# BoB_Brain_v05.net
KiCad netlist of a schematic drawn in EAGLE
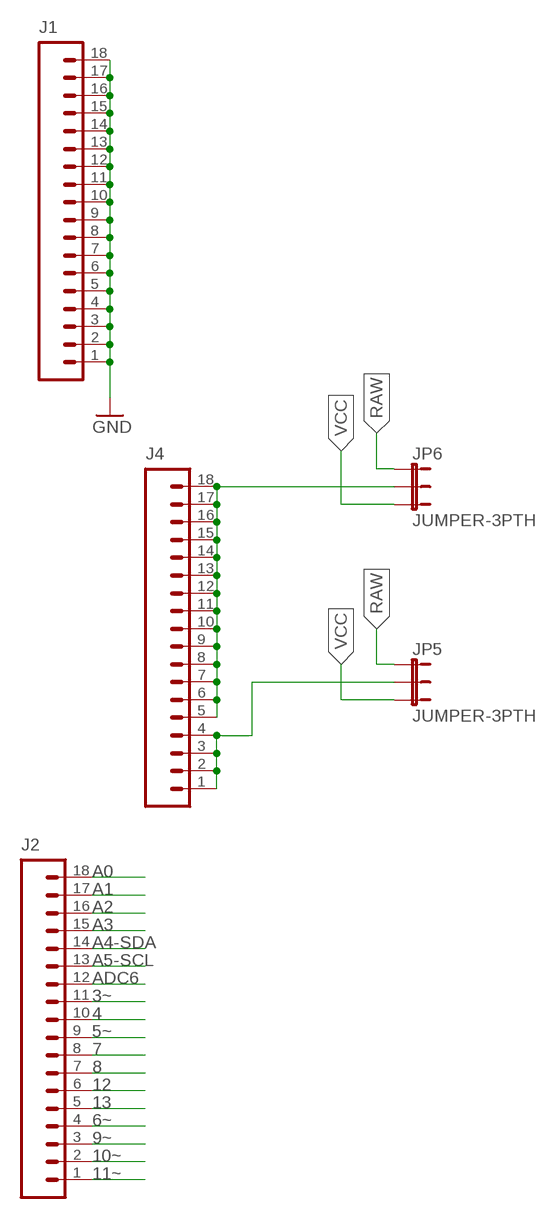
[diagram p0: schematic, sheet 1]
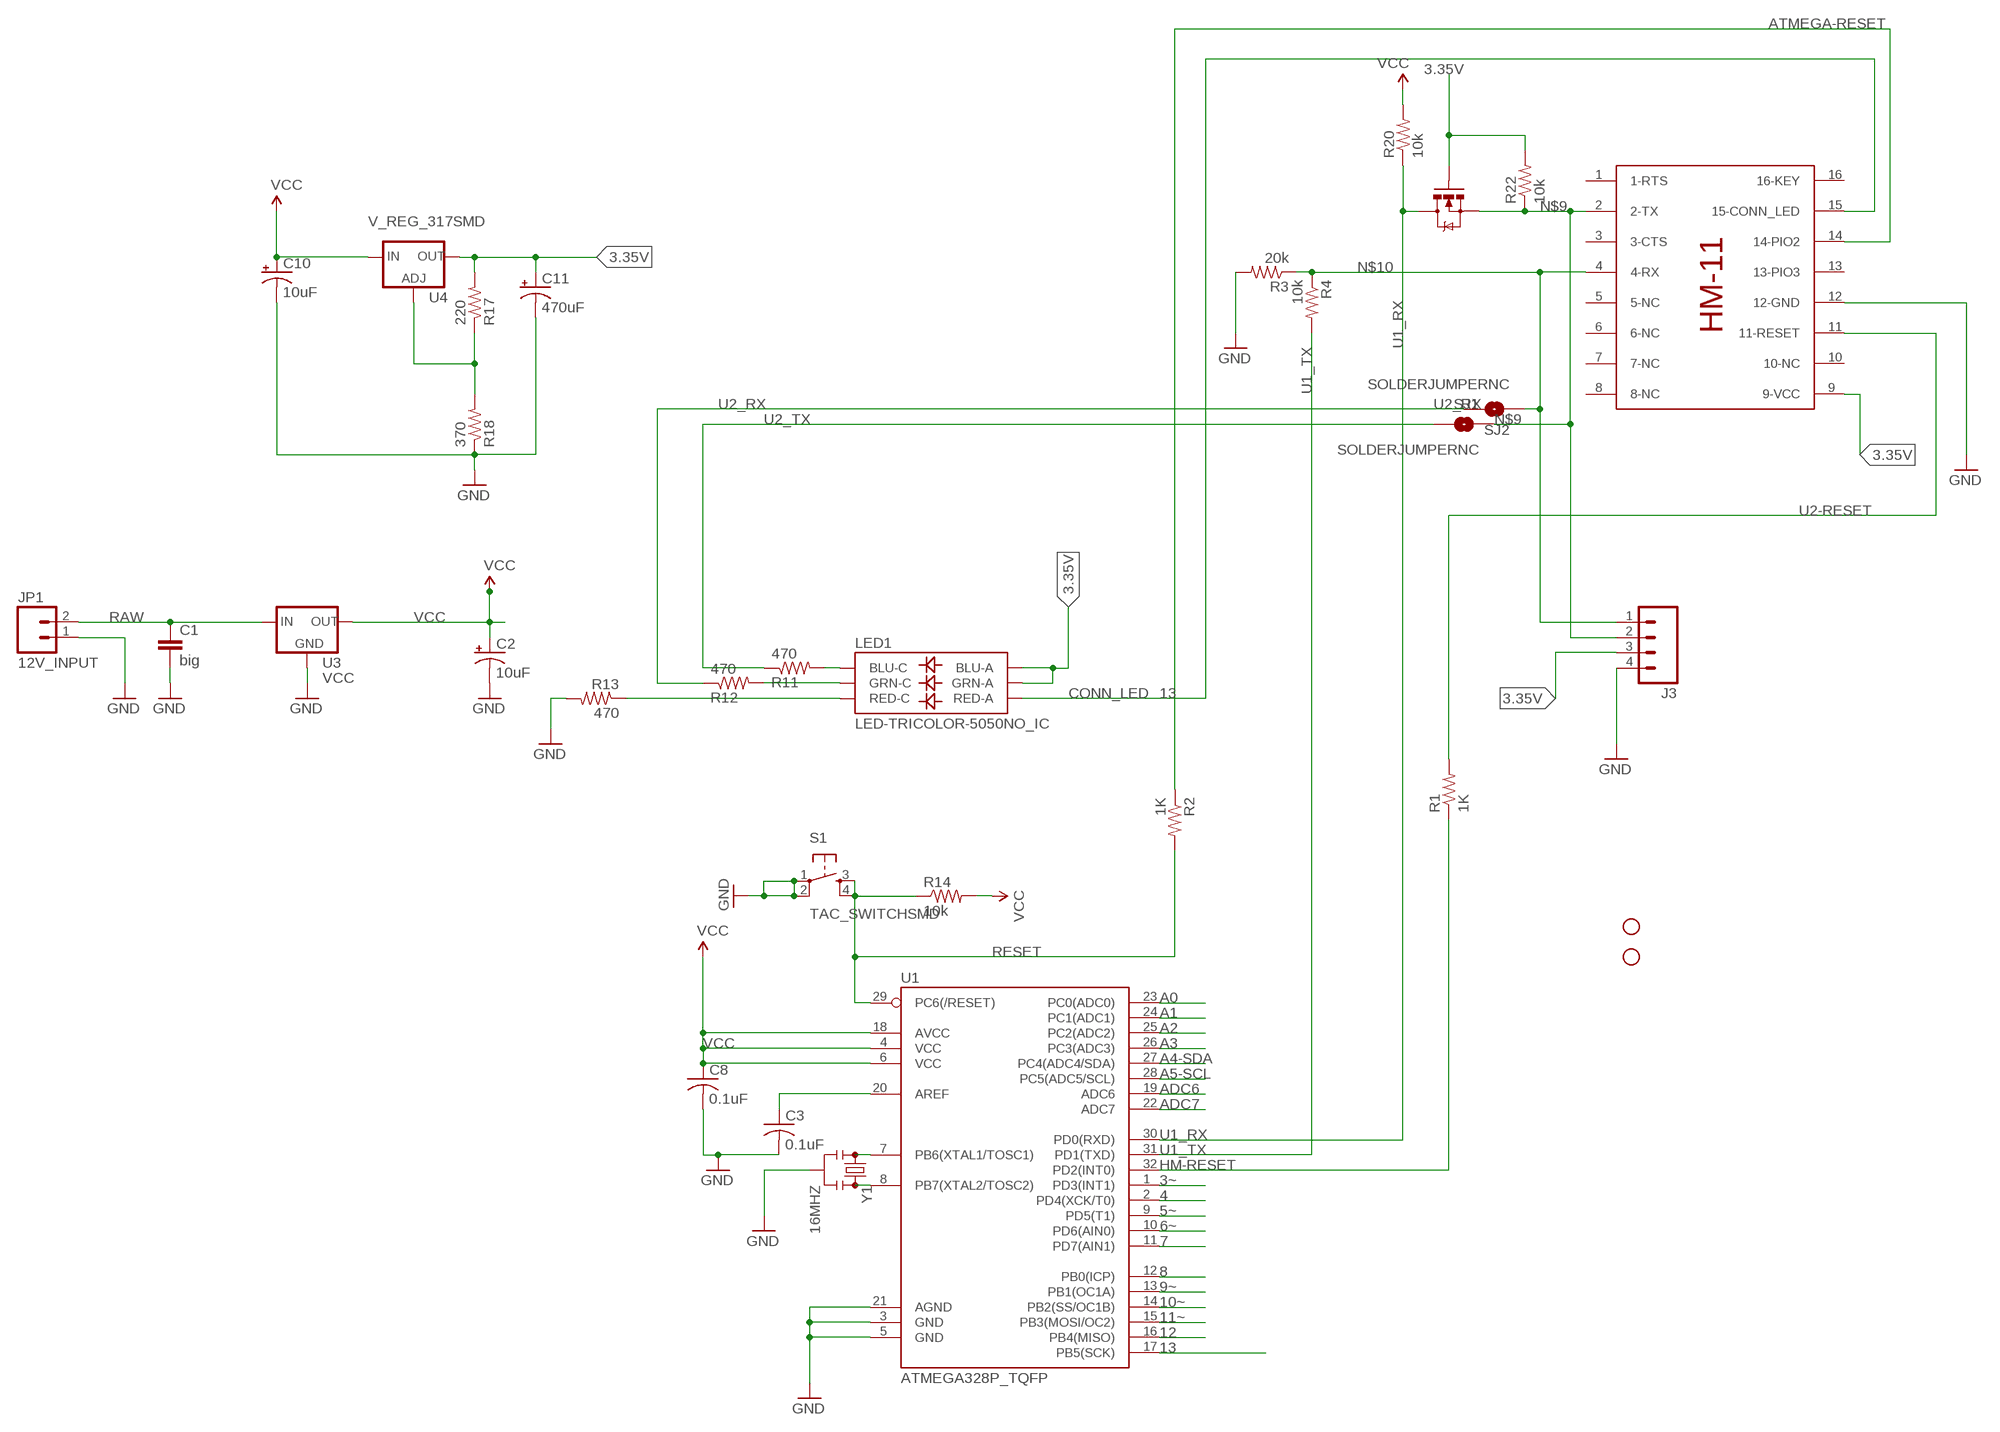
[diagram p1: schematic, sheet 2]

(export (version "E")
  (design (tool "Eeschema 10.0.6"))
  (components
    (comp (ref "C1")
      (value "big")
      (footprint "eagle-import:CAP-PTH-5MM")
      (libsource (lib "eagle-import") (part "CAPPTH1"))
    )
    (comp (ref "C2")
      (value "10uF")
      (footprint "eagle-import:EIA3528")
      (libsource (lib "eagle-import") (part "CAP_POL3528"))
    )
    (comp (ref "C3")
      (value "0.1uF")
      (footprint "eagle-import:C0402")
      (libsource (lib "eagle-import") (part "C-USC0402"))
    )
    (comp (ref "C8")
      (value "0.1uF")
      (footprint "eagle-import:C0402")
      (libsource (lib "eagle-import") (part "C-USC0402"))
    )
    (comp (ref "C10")
      (value "10uF")
      (footprint "eagle-import:EIA3528")
      (libsource (lib "eagle-import") (part "CAP_POL3528"))
    )
    (comp (ref "C11")
      (value "470uF")
      (footprint "eagle-import:CT3528")
      (libsource (lib "eagle-import") (part "CPOL-USCT3528"))
    )
    (comp (ref "H1")
      (value "STAND-OFF")
      (footprint "eagle-import:STAND-OFF")
      (libsource (lib "eagle-import") (part "STAND-OFF"))
    )
    (comp (ref "H2")
      (value "STAND-OFF")
      (footprint "eagle-import:STAND-OFF")
      (libsource (lib "eagle-import") (part "STAND-OFF"))
    )
    (comp (ref "J3")
      (value "M04PTH")
      (footprint "eagle-import:1X04")
      (libsource (lib "eagle-import") (part "M04PTH"))
    )
    (comp (ref "JP1")
      (value "12V_INPUT")
      (footprint "eagle-import:SCREWTERMINAL-5MM-2")
      (libsource (lib "eagle-import") (part "M025MM"))
    )
    (comp (ref "LED1")
      (value "LED-TRICOLOR-5050NO_IC")
      (footprint "eagle-import:LED-TRICOLOR-5050")
      (libsource (lib "eagle-import") (part "LED-TRICOLOR-5050NO_IC"))
    )
    (comp (ref "Q1")
      (value "MOSFET-NCHANNELAO3404A")
      (footprint "eagle-import:SOT23-3")
      (libsource (lib "eagle-import") (part "MOSFET-NCHANNELAO3404A"))
    )
    (comp (ref "R1")
      (value "1K")
      (footprint "eagle-import:R0805W")
      (libsource (lib "eagle-import") (part "R-US_R0805W"))
    )
    (comp (ref "R2")
      (value "1K")
      (footprint "eagle-import:R0805W")
      (libsource (lib "eagle-import") (part "R-US_R0805W"))
    )
    (comp (ref "R3")
      (value "20k")
      (footprint "eagle-import:R0805W")
      (libsource (lib "eagle-import") (part "R-US_R0805W"))
    )
    (comp (ref "R4")
      (value "10k")
      (footprint "eagle-import:R0805W")
      (libsource (lib "eagle-import") (part "R-US_R0805W"))
    )
    (comp (ref "R11")
      (value "470")
      (footprint "eagle-import:R0805W")
      (libsource (lib "eagle-import") (part "R-US_R0805W"))
    )
    (comp (ref "R12")
      (value "470")
      (footprint "eagle-import:R0805W")
      (libsource (lib "eagle-import") (part "R-US_R0805W"))
    )
    (comp (ref "R13")
      (value "470")
      (footprint "eagle-import:R0805W")
      (libsource (lib "eagle-import") (part "R-US_R0805W"))
    )
    (comp (ref "R14")
      (value "10k")
      (footprint "eagle-import:R0805W")
      (libsource (lib "eagle-import") (part "R-US_R0805W"))
    )
    (comp (ref "R17")
      (value "220")
      (footprint "eagle-import:R0805W")
      (libsource (lib "eagle-import") (part "R-US_R0805W"))
    )
    (comp (ref "R18")
      (value "370")
      (footprint "eagle-import:R0805W")
      (libsource (lib "eagle-import") (part "R-US_R0805W"))
    )
    (comp (ref "R20")
      (value "10k")
      (footprint "eagle-import:R0805W")
      (libsource (lib "eagle-import") (part "R-US_R0805W"))
    )
    (comp (ref "R22")
      (value "10k")
      (footprint "eagle-import:R0805W")
      (libsource (lib "eagle-import") (part "R-US_R0805W"))
    )
    (comp (ref "S1")
      (value "TAC_SWITCHSMD")
      (footprint "eagle-import:TACTILE-SWITCH-SMD")
      (libsource (lib "eagle-import") (part "TAC_SWITCHSMD"))
    )
    (comp (ref "SJ1")
      (value "SOLDERJUMPERNC")
      (footprint "eagle-import:SJ_2S")
      (libsource (lib "eagle-import") (part "SOLDERJUMPERNC"))
    )
    (comp (ref "SJ2")
      (value "SOLDERJUMPERNC")
      (footprint "eagle-import:SJ_2S")
      (libsource (lib "eagle-import") (part "SOLDERJUMPERNC"))
    )
    (comp (ref "U$1")
      (value "HM-11")
      (footprint "eagle-import:HM-11")
      (libsource (lib "eagle-import") (part "HM-11"))
    )
    (comp (ref "U1")
      (value "ATMEGA328P_TQFP")
      (footprint "eagle-import:TQFP32-08")
      (libsource (lib "eagle-import") (part "ATMEGA328P_TQFP"))
    )
    (comp (ref "U3")
      (value "VCC")
      (footprint "eagle-import:TO-252")
      (libsource (lib "eagle-import") (part "V_REG_78XX7812"))
    )
    (comp (ref "U4")
      (value "V_REG_317SMD")
      (footprint "eagle-import:SOT223")
      (libsource (lib "eagle-import") (part "V_REG_317SMD"))
    )
    (comp (ref "Y1")
      (value "16MHZ")
      (footprint "eagle-import:RESONATOR-SMD")
      (libsource (lib "eagle-import") (part "RESONATOR16MHZ"))
    )
    (comp (ref "J1")
      (value "M18_")
      (footprint "eagle-import:1X18")
      (libsource (lib "eagle-import") (part "M18_"))
    )
    (comp (ref "J2")
      (value "M18_")
      (footprint "eagle-import:1X18")
      (libsource (lib "eagle-import") (part "M18_"))
    )
    (comp (ref "J4")
      (value "M18_")
      (footprint "eagle-import:1X18")
      (libsource (lib "eagle-import") (part "M18_"))
    )
    (comp (ref "JP5")
      (value "JUMPER-3PTH")
      (footprint "eagle-import:1X03")
      (libsource (lib "eagle-import") (part "JUMPER-3PTH"))
    )
    (comp (ref "JP6")
      (value "JUMPER-3PTH")
      (footprint "eagle-import:1X03")
      (libsource (lib "eagle-import") (part "JUMPER-3PTH"))
    )
  )
  (nets
    (net (code "1") (name "3.35V") (class "Default")
      (node (ref "C11") (pin "-") (pinfunction "+_-") (pintype "passive"))
      (node (ref "J3") (pin "3") (pinfunction "3_3") (pintype "passive"))
      (node (ref "LED1") (pin "1") (pinfunction "GRN-A_1") (pintype "bidirectional"))
      (node (ref "LED1") (pin "3") (pinfunction "BLU-A_3") (pintype "bidirectional"))
      (node (ref "Q1") (pin "1") (pinfunction "G_1") (pintype "passive"))
      (node (ref "R17") (pin "2") (pinfunction "2_2") (pintype "passive"))
      (node (ref "R22") (pin "2") (pinfunction "2_2") (pintype "passive"))
      (node (ref "U$1") (pin "9") (pinfunction "9-VCC_9") (pintype "bidirectional"))
      (node (ref "U4") (pin "2") (pinfunction "OUT_2") (pintype "output"))
    )
    (net (code "2") (name "3~{}") (class "Default")
      (node (ref "J2") (pin "18") (pinfunction "18_18") (pintype "passive"))
      (node (ref "U1") (pin "1") (pinfunction "PD3(INT1)_1") (pintype "bidirectional"))
    )
    (net (code "3") (name "4") (class "Default")
      (node (ref "J2") (pin "17") (pinfunction "17_17") (pintype "passive"))
      (node (ref "U1") (pin "2") (pinfunction "PD4(XCK/T0)_2") (pintype "bidirectional"))
    )
    (net (code "4") (name "5~{}") (class "Default")
      (node (ref "J2") (pin "9") (pinfunction "9_9") (pintype "passive"))
      (node (ref "U1") (pin "9") (pinfunction "PD5(T1)_9") (pintype "bidirectional"))
    )
    (net (code "5") (name "6~{}") (class "Default")
      (node (ref "J2") (pin "4") (pinfunction "4_4") (pintype "passive"))
      (node (ref "U1") (pin "10") (pinfunction "PD6(AIN0)_10") (pintype "bidirectional"))
    )
    (net (code "6") (name "7") (class "Default")
      (node (ref "J2") (pin "8") (pinfunction "8_8") (pintype "passive"))
      (node (ref "U1") (pin "11") (pinfunction "PD7(AIN1)_11") (pintype "bidirectional"))
    )
    (net (code "7") (name "8") (class "Default")
      (node (ref "J2") (pin "7") (pinfunction "7_7") (pintype "passive"))
      (node (ref "U1") (pin "12") (pinfunction "PB0(ICP)_12") (pintype "bidirectional"))
    )
    (net (code "8") (name "9~{}") (class "Default")
      (node (ref "J2") (pin "3") (pinfunction "3_3") (pintype "passive"))
      (node (ref "U1") (pin "13") (pinfunction "PB1(OC1A)_13") (pintype "bidirectional"))
    )
    (net (code "9") (name "10~{}") (class "Default")
      (node (ref "J2") (pin "2") (pinfunction "2_2") (pintype "passive"))
      (node (ref "U1") (pin "14") (pinfunction "PB2(SS/OC1B)_14") (pintype "bidirectional"))
    )
    (net (code "10") (name "11~{}") (class "Default")
      (node (ref "J2") (pin "1") (pinfunction "1_1") (pintype "passive"))
      (node (ref "U1") (pin "15") (pinfunction "PB3(MOSI/OC2)_15") (pintype "bidirectional"))
    )
    (net (code "11") (name "12") (class "Default")
      (node (ref "J2") (pin "6") (pinfunction "6_6") (pintype "passive"))
      (node (ref "U1") (pin "16") (pinfunction "PB4(MISO)_16") (pintype "bidirectional"))
    )
    (net (code "12") (name "13") (class "Default")
      (node (ref "J2") (pin "5") (pinfunction "5_5") (pintype "passive"))
      (node (ref "U1") (pin "17") (pinfunction "PB5(SCK)_17") (pintype "bidirectional"))
    )
    (net (code "13") (name "A0") (class "Default")
      (node (ref "J2") (pin "12") (pinfunction "12_12") (pintype "passive"))
      (node (ref "U1") (pin "23") (pinfunction "PC0(ADC0)_23") (pintype "bidirectional"))
    )
    (net (code "14") (name "A1") (class "Default")
      (node (ref "J2") (pin "10") (pinfunction "10_10") (pintype "passive"))
      (node (ref "U1") (pin "24") (pinfunction "PC1(ADC1)_24") (pintype "bidirectional"))
    )
    (net (code "15") (name "A2") (class "Default")
      (node (ref "J2") (pin "16") (pinfunction "16_16") (pintype "passive"))
      (node (ref "U1") (pin "25") (pinfunction "PC2(ADC2)_25") (pintype "bidirectional"))
    )
    (net (code "16") (name "A3") (class "Default")
      (node (ref "J2") (pin "13") (pinfunction "13_13") (pintype "passive"))
      (node (ref "U1") (pin "26") (pinfunction "PC3(ADC3)_26") (pintype "bidirectional"))
    )
    (net (code "17") (name "A4-SDA") (class "Default")
      (node (ref "J2") (pin "14") (pinfunction "14_14") (pintype "passive"))
      (node (ref "U1") (pin "27") (pinfunction "PC4(ADC4/SDA)_27") (pintype "bidirectional"))
    )
    (net (code "18") (name "A5-SCL") (class "Default")
      (node (ref "J2") (pin "15") (pinfunction "15_15") (pintype "passive"))
      (node (ref "U1") (pin "28") (pinfunction "PC5(ADC5/SCL)_28") (pintype "bidirectional"))
    )
    (net (code "19") (name "ADC6") (class "Default")
      (node (ref "J2") (pin "11") (pinfunction "11_11") (pintype "passive"))
      (node (ref "U1") (pin "19") (pinfunction "ADC6_19") (pintype "bidirectional"))
    )
    (net (code "20") (name "ADC7") (class "Default")
      (node (ref "U1") (pin "22") (pinfunction "ADC7_22") (pintype "bidirectional"))
    )
    (net (code "21") (name "ATMEGA-RESET") (class "Default")
      (node (ref "R2") (pin "1") (pinfunction "1_1") (pintype "passive"))
      (node (ref "U$1") (pin "14") (pinfunction "14-PIO2_14") (pintype "bidirectional"))
    )
    (net (code "22") (name "CONN_LED") (class "Default")
      (node (ref "LED1") (pin "2") (pinfunction "RED-A_2") (pintype "bidirectional"))
      (node (ref "U$1") (pin "15") (pinfunction "15-CONN_LED_15") (pintype "bidirectional"))
    )
    (net (code "23") (name "GND") (class "Default")
      (node (ref "C1") (pin "2") (pinfunction "2_2") (pintype "passive"))
      (node (ref "C10") (pin "C") (pinfunction "-_C") (pintype "passive"))
      (node (ref "C11") (pin "+") (pinfunction "-_+") (pintype "passive"))
      (node (ref "C2") (pin "C") (pinfunction "-_C") (pintype "passive"))
      (node (ref "C3") (pin "2") (pinfunction "2_2") (pintype "passive"))
      (node (ref "C8") (pin "2") (pinfunction "2_2") (pintype "passive"))
      (node (ref "J1") (pin "1") (pinfunction "1_1") (pintype "passive"))
      (node (ref "J1") (pin "10") (pinfunction "10_10") (pintype "passive"))
      (node (ref "J1") (pin "11") (pinfunction "11_11") (pintype "passive"))
      (node (ref "J1") (pin "12") (pinfunction "12_12") (pintype "passive"))
      (node (ref "J1") (pin "13") (pinfunction "13_13") (pintype "passive"))
      (node (ref "J1") (pin "14") (pinfunction "14_14") (pintype "passive"))
      (node (ref "J1") (pin "15") (pinfunction "15_15") (pintype "passive"))
      (node (ref "J1") (pin "16") (pinfunction "16_16") (pintype "passive"))
      (node (ref "J1") (pin "17") (pinfunction "17_17") (pintype "passive"))
      (node (ref "J1") (pin "18") (pinfunction "18_18") (pintype "passive"))
      (node (ref "J1") (pin "2") (pinfunction "2_2") (pintype "passive"))
      (node (ref "J1") (pin "3") (pinfunction "3_3") (pintype "passive"))
      (node (ref "J1") (pin "4") (pinfunction "4_4") (pintype "passive"))
      (node (ref "J1") (pin "5") (pinfunction "5_5") (pintype "passive"))
      (node (ref "J1") (pin "6") (pinfunction "6_6") (pintype "passive"))
      (node (ref "J1") (pin "7") (pinfunction "7_7") (pintype "passive"))
      (node (ref "J1") (pin "8") (pinfunction "8_8") (pintype "passive"))
      (node (ref "J1") (pin "9") (pinfunction "9_9") (pintype "passive"))
      (node (ref "J3") (pin "4") (pinfunction "4_4") (pintype "passive"))
      (node (ref "JP1") (pin "1") (pinfunction "1_1") (pintype "passive"))
      (node (ref "R13") (pin "2") (pinfunction "2_2") (pintype "passive"))
      (node (ref "R18") (pin "1") (pinfunction "1_1") (pintype "passive"))
      (node (ref "R3") (pin "2") (pinfunction "2_2") (pintype "passive"))
      (node (ref "S1") (pin "1") (pinfunction "1_1") (pintype "passive"))
      (node (ref "S1") (pin "2") (pinfunction "2_2") (pintype "passive"))
      (node (ref "U$1") (pin "12") (pinfunction "12-GND_12") (pintype "bidirectional"))
      (node (ref "U1") (pin "21") (pinfunction "AGND_21") (pintype "bidirectional"))
      (node (ref "U1") (pin "3") (pinfunction "GND_3") (pintype "bidirectional"))
      (node (ref "U1") (pin "5") (pinfunction "GND_5") (pintype "bidirectional"))
      (node (ref "U3") (pin "3") (pinfunction "GND_3") (pintype "input"))
      (node (ref "Y1") (pin "2") (pinfunction "2_2") (pintype "passive"))
    )
    (net (code "24") (name "HM-RESET") (class "Default")
      (node (ref "R1") (pin "1") (pinfunction "1_1") (pintype "passive"))
      (node (ref "U1") (pin "32") (pinfunction "PD2(INT0)_32") (pintype "bidirectional"))
    )
    (net (code "25") (name "N$9") (class "Default")
      (node (ref "J3") (pin "2") (pinfunction "2_2") (pintype "passive"))
      (node (ref "Q1") (pin "2") (pinfunction "S_2") (pintype "passive"))
      (node (ref "R22") (pin "1") (pinfunction "1_1") (pintype "passive"))
      (node (ref "SJ1") (pin "1") (pinfunction "1_1") (pintype "passive"))
      (node (ref "U$1") (pin "2") (pinfunction "2-TX_2") (pintype "bidirectional"))
    )
    (net (code "26") (name "N$10") (class "Default")
      (node (ref "J3") (pin "1") (pinfunction "1_1") (pintype "passive"))
      (node (ref "R3") (pin "1") (pinfunction "1_1") (pintype "passive"))
      (node (ref "R4") (pin "1") (pinfunction "1_1") (pintype "passive"))
      (node (ref "SJ2") (pin "1") (pinfunction "1_1") (pintype "passive"))
      (node (ref "U$1") (pin "4") (pinfunction "4-RX_4") (pintype "bidirectional"))
    )
    (net (code "27") (name "Net-(J4-Pad1)") (class "Default")
      (node (ref "J4") (pin "1") (pinfunction "1_1") (pintype "passive"))
      (node (ref "J4") (pin "2") (pinfunction "2_2") (pintype "passive"))
      (node (ref "J4") (pin "3") (pinfunction "3_3") (pintype "passive"))
      (node (ref "J4") (pin "4") (pinfunction "4_4") (pintype "passive"))
      (node (ref "JP5") (pin "2") (pinfunction "2_2") (pintype "passive"))
    )
    (net (code "28") (name "Net-(J4-Pad10)") (class "Default")
      (node (ref "J4") (pin "10") (pinfunction "10_10") (pintype "passive"))
      (node (ref "J4") (pin "11") (pinfunction "11_11") (pintype "passive"))
      (node (ref "J4") (pin "12") (pinfunction "12_12") (pintype "passive"))
      (node (ref "J4") (pin "13") (pinfunction "13_13") (pintype "passive"))
      (node (ref "J4") (pin "14") (pinfunction "14_14") (pintype "passive"))
      (node (ref "J4") (pin "15") (pinfunction "15_15") (pintype "passive"))
      (node (ref "J4") (pin "16") (pinfunction "16_16") (pintype "passive"))
      (node (ref "J4") (pin "17") (pinfunction "17_17") (pintype "passive"))
      (node (ref "J4") (pin "18") (pinfunction "18_18") (pintype "passive"))
      (node (ref "J4") (pin "5") (pinfunction "5_5") (pintype "passive"))
      (node (ref "J4") (pin "6") (pinfunction "6_6") (pintype "passive"))
      (node (ref "J4") (pin "7") (pinfunction "7_7") (pintype "passive"))
      (node (ref "J4") (pin "8") (pinfunction "8_8") (pintype "passive"))
      (node (ref "J4") (pin "9") (pinfunction "9_9") (pintype "passive"))
      (node (ref "JP6") (pin "2") (pinfunction "2_2") (pintype "passive"))
    )
    (net (code "29") (name "Net-(LED1-BLU-C)") (class "Default")
      (node (ref "LED1") (pin "4") (pinfunction "BLU-C_4") (pintype "bidirectional"))
      (node (ref "R11") (pin "2") (pinfunction "2_2") (pintype "passive"))
    )
    (net (code "30") (name "Net-(LED1-GRN-C)") (class "Default")
      (node (ref "LED1") (pin "6") (pinfunction "GRN-C_6") (pintype "bidirectional"))
      (node (ref "R12") (pin "2") (pinfunction "2_2") (pintype "passive"))
    )
    (net (code "31") (name "Net-(LED1-RED-C)") (class "Default")
      (node (ref "LED1") (pin "5") (pinfunction "RED-C_5") (pintype "bidirectional"))
      (node (ref "R13") (pin "1") (pinfunction "1_1") (pintype "passive"))
    )
    (net (code "32") (name "Net-(U1-AREF)") (class "Default")
      (node (ref "C3") (pin "1") (pinfunction "1_1") (pintype "passive"))
      (node (ref "U1") (pin "20") (pinfunction "AREF_20") (pintype "bidirectional"))
    )
    (net (code "33") (name "Net-(U1-PB6(XTAL1{slash}TOSC1))") (class "Default")
      (node (ref "U1") (pin "7") (pinfunction "PB6(XTAL1/TOSC1)_7") (pintype "bidirectional"))
      (node (ref "Y1") (pin "1") (pinfunction "1_1") (pintype "passive"))
    )
    (net (code "34") (name "Net-(U1-PB7(XTAL2{slash}TOSC2))") (class "Default")
      (node (ref "U1") (pin "8") (pinfunction "PB7(XTAL2/TOSC2)_8") (pintype "bidirectional"))
      (node (ref "Y1") (pin "3") (pinfunction "3_3") (pintype "passive"))
    )
    (net (code "35") (name "Net-(U4-ADJ)") (class "Default")
      (node (ref "R17") (pin "1") (pinfunction "1_1") (pintype "passive"))
      (node (ref "R18") (pin "2") (pinfunction "2_2") (pintype "passive"))
      (node (ref "U4") (pin "1") (pinfunction "ADJ_1") (pintype "input"))
    )
    (net (code "36") (name "RAW") (class "Default")
      (node (ref "C1") (pin "1") (pinfunction "1_1") (pintype "passive"))
      (node (ref "JP1") (pin "2") (pinfunction "2_2") (pintype "passive"))
      (node (ref "JP5") (pin "1") (pinfunction "1_1") (pintype "passive"))
      (node (ref "JP6") (pin "1") (pinfunction "1_1") (pintype "passive"))
      (node (ref "U3") (pin "1") (pinfunction "IN_1") (pintype "input"))
    )
    (net (code "37") (name "RESET") (class "Default")
      (node (ref "R14") (pin "1") (pinfunction "1_1") (pintype "passive"))
      (node (ref "R2") (pin "2") (pinfunction "2_2") (pintype "passive"))
      (node (ref "S1") (pin "3") (pinfunction "3_3") (pintype "passive"))
      (node (ref "S1") (pin "4") (pinfunction "4_4") (pintype "passive"))
      (node (ref "U1") (pin "29") (pinfunction "PC6(/RESET)_29") (pintype "bidirectional"))
    )
    (net (code "38") (name "U1_RX") (class "Default")
      (node (ref "Q1") (pin "3") (pinfunction "D_3") (pintype "passive"))
      (node (ref "R20") (pin "1") (pinfunction "1_1") (pintype "passive"))
      (node (ref "U1") (pin "30") (pinfunction "PD0(RXD)_30") (pintype "bidirectional"))
    )
    (net (code "39") (name "U1_TX") (class "Default")
      (node (ref "R4") (pin "2") (pinfunction "2_2") (pintype "passive"))
      (node (ref "U1") (pin "31") (pinfunction "PD1(TXD)_31") (pintype "bidirectional"))
    )
    (net (code "40") (name "U2-RESET") (class "Default")
      (node (ref "R1") (pin "2") (pinfunction "2_2") (pintype "passive"))
      (node (ref "U$1") (pin "11") (pinfunction "11-RESET_11") (pintype "bidirectional"))
    )
    (net (code "41") (name "U2_RX") (class "Default")
      (node (ref "R12") (pin "1") (pinfunction "1_1") (pintype "passive"))
      (node (ref "SJ2") (pin "2") (pinfunction "2_2") (pintype "passive"))
    )
    (net (code "42") (name "U2_TX") (class "Default")
      (node (ref "R11") (pin "1") (pinfunction "1_1") (pintype "passive"))
      (node (ref "SJ1") (pin "2") (pinfunction "2_2") (pintype "passive"))
    )
    (net (code "43") (name "VCC") (class "Default")
      (node (ref "C10") (pin "A") (pinfunction "+_A") (pintype "passive"))
      (node (ref "C2") (pin "A") (pinfunction "+_A") (pintype "passive"))
      (node (ref "C8") (pin "1") (pinfunction "1_1") (pintype "passive"))
      (node (ref "JP5") (pin "3") (pinfunction "3_3") (pintype "passive"))
      (node (ref "JP6") (pin "3") (pinfunction "3_3") (pintype "passive"))
      (node (ref "R14") (pin "2") (pinfunction "2_2") (pintype "passive"))
      (node (ref "R20") (pin "2") (pinfunction "2_2") (pintype "passive"))
      (node (ref "U1") (pin "18") (pinfunction "AVCC_18") (pintype "bidirectional"))
      (node (ref "U1") (pin "4") (pinfunction "VCC_4") (pintype "bidirectional"))
      (node (ref "U1") (pin "6") (pinfunction "VCC_6") (pintype "bidirectional"))
      (node (ref "U3") (pin "2") (pinfunction "OUT_2") (pintype "passive"))
      (node (ref "U4") (pin "3") (pinfunction "IN_3") (pintype "input"))
    )
    (net (code "44") (name "unconnected-(U$1-1-RTS-Pad1)") (class "Default")
      (node (ref "U$1") (pin "1") (pinfunction "1-RTS_1") (pintype "bidirectional"))
    )
    (net (code "45") (name "unconnected-(U$1-3-CTS-Pad3)") (class "Default")
      (node (ref "U$1") (pin "3") (pinfunction "3-CTS_3") (pintype "bidirectional"))
    )
    (net (code "46") (name "unconnected-(U$1-5-NC-Pad5)") (class "Default")
      (node (ref "U$1") (pin "5") (pinfunction "5-NC_5") (pintype "bidirectional"))
    )
    (net (code "47") (name "unconnected-(U$1-6-NC-Pad6)") (class "Default")
      (node (ref "U$1") (pin "6") (pinfunction "6-NC_6") (pintype "bidirectional"))
    )
    (net (code "48") (name "unconnected-(U$1-7-NC-Pad7)") (class "Default")
      (node (ref "U$1") (pin "7") (pinfunction "7-NC_7") (pintype "bidirectional"))
    )
    (net (code "49") (name "unconnected-(U$1-8-NC-Pad8)") (class "Default")
      (node (ref "U$1") (pin "8") (pinfunction "8-NC_8") (pintype "bidirectional"))
    )
    (net (code "50") (name "unconnected-(U$1-10-NC-Pad10)") (class "Default")
      (node (ref "U$1") (pin "10") (pinfunction "10-NC_10") (pintype "bidirectional"))
    )
    (net (code "51") (name "unconnected-(U$1-13-PIO3-Pad13)") (class "Default")
      (node (ref "U$1") (pin "13") (pinfunction "13-PIO3_13") (pintype "bidirectional"))
    )
    (net (code "52") (name "unconnected-(U$1-16-KEY-Pad16)") (class "Default")
      (node (ref "U$1") (pin "16") (pinfunction "16-KEY_16") (pintype "bidirectional"))
    )
  )
)
